# Practica.net
KiCad netlist of a schematic drawn in Altium Designer
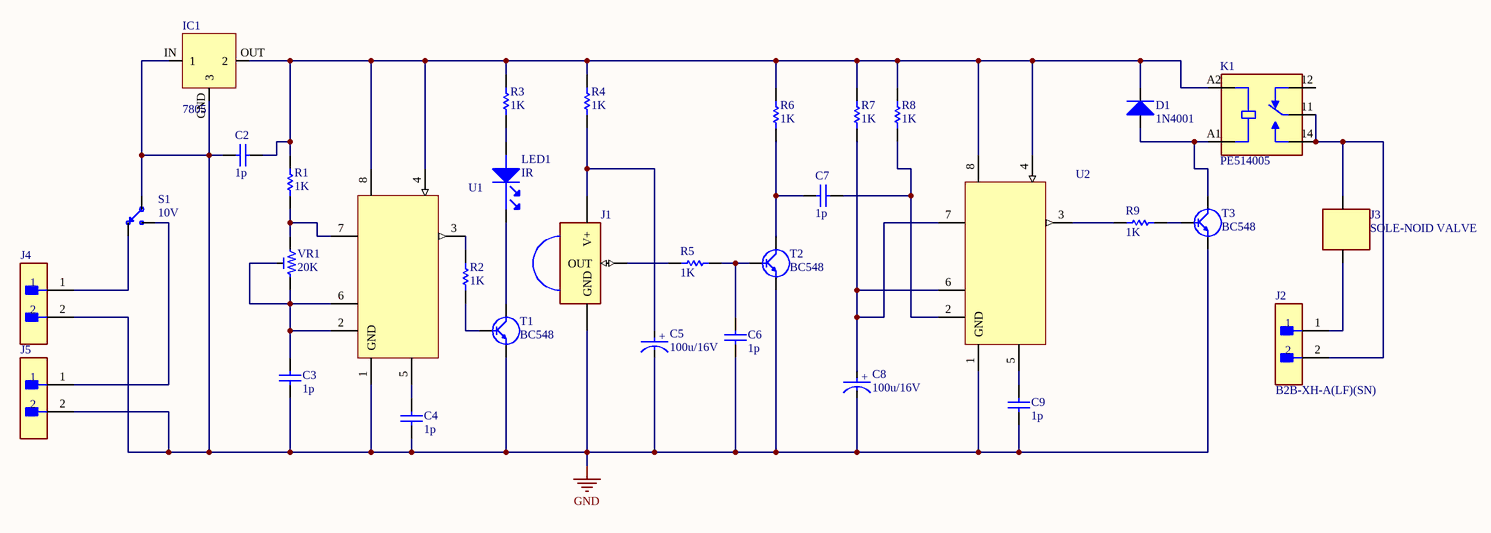
[diagram p0: Practica.SchDoc]

(export (version "E")
  (design (tool "Eeschema 10.0.6"))
  (components
    (comp (ref "C2")
      (value "1p")
      (footprint "CAPC1005X55N")
      (description "Capacitor")
      (libsource (lib "Practica_Schlib1") (part "Capacitor"))
    )
    (comp (ref "C3")
      (value "1p")
      (footprint "CAPC1005X55N")
      (description "Capacitor")
      (libsource (lib "Practica_Schlib1") (part "Capacitor"))
    )
    (comp (ref "C4")
      (value "1p")
      (footprint "CAPC1005X55N")
      (description "Capacitor")
      (libsource (lib "Practica_Schlib1") (part "Capacitor"))
    )
    (comp (ref "C5")
      (value "100u/16V")
      (footprint "WCAP-ASLI_D4H5.5")
      (description "15uF 6.3V  ±20% 3.5Ω 1206  SMD Tantalum Capacitor")
      (fields (field (name "TOLERANCE") "20%") (field (name "MANUFACTURER") "Wurth Electronics"))
      (libsource (lib "Practica_Schlib1") (part "a00bbbee19879c290e62620ae7e47b1"))
    )
    (comp (ref "C6")
      (value "1p")
      (footprint "CAPC1005X55N")
      (description "Capacitor")
      (libsource (lib "Practica_Schlib1") (part "Capacitor"))
    )
    (comp (ref "C7")
      (value "1p")
      (footprint "CAPC1005X55N")
      (description "Capacitor")
      (libsource (lib "Practica_Schlib1") (part "Capacitor"))
    )
    (comp (ref "C8")
      (value "100u/16V")
      (footprint "WCAP-ASLI_D4H5.5")
      (description "15uF 6.3V  ±20% 3.5Ω 1206  SMD Tantalum Capacitor")
      (fields (field (name "TOLERANCE") "20%") (field (name "MANUFACTURER") "Wurth Electronics"))
      (libsource (lib "Practica_Schlib1") (part "a00bbbee19879c290e62620ae7e47b1"))
    )
    (comp (ref "C9")
      (value "1p")
      (footprint "CAPC1005X55N")
      (description "Capacitor")
      (libsource (lib "Practica_Schlib1") (part "Capacitor"))
    )
    (comp (ref "D1")
      (value "1N4001")
      (footprint "DIOAD1036W78L470D235")
      (fields (field (name "MANUFACTURER") "Good-Ark"))
      (libsource (lib "Practica_Schlib1") (part "1N4001"))
    )
    (comp (ref "IC1")
      (value "7805")
      (footprint "78XXS")
      (description "Fixed Positive Standard Regulator, 5VBIPolar, PSSO2")
      (fields (field (name "MANUFACTURER") "onsemi") (field (name "MANUFACTURER PART NUMBER") "MC7805BDTG"))
      (libsource (lib "Practica_Schlib1") (part "IC1"))
    )
    (comp (ref "J1")
      (value "TSOP1738")
      (footprint "TSOP17XX")
      (description "IR Remote Receiver 38KHz 35m 3-Pin")
      (fields (field (name "MP") "TSOP1738.") (field (name "MF") "Vishay"))
      (libsource (lib "Practica_Schlib1") (part "TSOP1738"))
    )
    (comp (ref "J2")
      (value "B2B-XH-A(LF)(SN)")
      (footprint "FP-B2B-XH-A_LF_SN-MFG")
      (description "CONN HEADER VERT 2POS 2.5MM")
      (libsource (lib "Practica_Schlib1") (part "CON2"))
    )
    (comp (ref "J3")
      (value "SOLE-NOID VALVE")
      (footprint "PHOENIX_1904147")
      (fields (field (name "MF") "Phoenix Contact") (field (name "MP") "1904147"))
      (libsource (lib "Practica_Schlib1") (part "SOLE-NOID VALVE"))
    )
    (comp (ref "J4")
      (value "B2B-XH-A(LF)(SN)")
      (footprint "FP-B2B-XH-A_LF_SN-MFG")
      (description "CONN HEADER VERT 2POS 2.5MM")
      (libsource (lib "Practica_Schlib1") (part "CON2"))
    )
    (comp (ref "J5")
      (value "B2B-XH-A(LF)(SN)")
      (footprint "FP-B2B-XH-A_LF_SN-MFG")
      (description "CONN HEADER VERT 2POS 2.5MM")
      (libsource (lib "Practica_Schlib1") (part "CON2"))
    )
    (comp (ref "K1")
      (value "PE514005")
      (footprint "RELAY_PE514005")
      (description "Shrack, Relay,miniature,PCB,SPDT,5A,5Vdc coil, 1-1393219-7 ¦ TE Connectivity PE514005")
      (fields (field (name "MF") "TE Connectivity"))
      (libsource (lib "Practica_Schlib1") (part "PE514005"))
    )
    (comp (ref "LED1")
      (value "IR")
      (footprint "LED3MM")
      (description "LED SM 0603 3V -/1000/-MCD GREEN")
      (fields
        (field (name "MANUFACTURER") "Visual Communications")
        (field (name "MANUFACTURER PART NUMBER") "LSM0603453V")
      )
      (libsource (lib "Practica_Schlib1") (part "LED"))
    )
    (comp (ref "R1")
      (value "1K")
      (footprint "RESC1005X40N")
      (description "Resistor")
      (libsource (lib "Practica_Schlib1") (part "Resistor"))
    )
    (comp (ref "R2")
      (value "1K")
      (footprint "RESC1005X40N")
      (description "Resistor")
      (libsource (lib "Practica_Schlib1") (part "Resistor"))
    )
    (comp (ref "R3")
      (value "1K")
      (footprint "RESC1005X40N")
      (description "Resistor")
      (libsource (lib "Practica_Schlib1") (part "Resistor"))
    )
    (comp (ref "R4")
      (value "1K")
      (footprint "RESC1005X40N")
      (description "Resistor")
      (libsource (lib "Practica_Schlib1") (part "Resistor"))
    )
    (comp (ref "R5")
      (value "1K")
      (footprint "RESC1005X40N")
      (description "Resistor")
      (libsource (lib "Practica_Schlib1") (part "Resistor"))
    )
    (comp (ref "R6")
      (value "1K")
      (footprint "RESC1005X40N")
      (description "Resistor")
      (libsource (lib "Practica_Schlib1") (part "Resistor"))
    )
    (comp (ref "R7")
      (value "1K")
      (footprint "RESC1005X40N")
      (description "Resistor")
      (libsource (lib "Practica_Schlib1") (part "Resistor"))
    )
    (comp (ref "R8")
      (value "1K")
      (footprint "RESC1005X40N")
      (description "Resistor")
      (libsource (lib "Practica_Schlib1") (part "Resistor"))
    )
    (comp (ref "R9")
      (value "1K")
      (footprint "RESC1005X40N")
      (description "Resistor")
      (libsource (lib "Practica_Schlib1") (part "Resistor"))
    )
    (comp (ref "S1")
      (value "10V")
      (footprint "SW_A101SYZQ04")
      (description "Toggle Switch")
      (fields
        (field (name "MANUFACTURER") "E-Switch")
        (field (name "MANUFACTURER PART NUMBER") "100SP2T1B1M1QEH")
      )
      (libsource (lib "Practica_Schlib1") (part "switch"))
    )
    (comp (ref "T1")
      (value "BC548")
      (footprint "TO92250P510H770-3")
      (description "Bipolar (BJT) Transistor NPN 30 V 100 mA 300MHz 500 mW Through Hole TO-92-3")
      (fields (field (name "MANUFACTURER") "onsemi"))
      (libsource (lib "Practica_Schlib1") (part "BC548"))
    )
    (comp (ref "T2")
      (value "BC548")
      (footprint "TO92250P510H770-3")
      (description "Bipolar (BJT) Transistor NPN 30 V 100 mA 300MHz 500 mW Through Hole TO-92-3")
      (fields (field (name "MANUFACTURER") "onsemi"))
      (libsource (lib "Practica_Schlib1") (part "BC548"))
    )
    (comp (ref "T3")
      (value "BC548")
      (footprint "TO92250P510H770-3")
      (description "Bipolar (BJT) Transistor NPN 30 V 100 mA 300MHz 500 mW Through Hole TO-92-3")
      (fields (field (name "MANUFACTURER") "onsemi"))
      (libsource (lib "Practica_Schlib1") (part "BC548"))
    )
    (comp (ref "U1")
      (value "LMC555CMM/NOPB")
      (footprint "DGK0008A_L")
      (description "CMOS Timer, 8-pin Mini SOIC, Pb-Free")
      (fields (field (name "MANUFACTURER") "Texas Instruments"))
      (libsource (lib "Practica_Schlib1") (part "LM555"))
    )
    (comp (ref "U2")
      (value "LMC555CMM/NOPB")
      (footprint "DGK0008A_L")
      (description "CMOS Timer, 8-pin Mini SOIC, Pb-Free")
      (fields (field (name "MANUFACTURER") "Texas Instruments"))
      (libsource (lib "Practica_Schlib1") (part "LM555"))
    )
    (comp (ref "VR1")
      (value "20K")
      (footprint "TRIM_PV36W203C01B00")
      (description "20 kOhms 0.5W, 1/2W PC Pins Through Hole Trimmer Potentiometer Cermet 25.0 Turn Top Adjustment")
      (fields
        (field (name "MANUFACTURER") "Bourns")
        (field (name "MANUFACTURER PART NUMBER") "PV36W203C01B00")
      )
      (libsource (lib "Practica_Schlib1") (part "VR"))
    )
  )
  (nets
    (net (code "1") (name "GND") (class "Default")
      (node (ref "C2") (pin "1") (pinfunction "1_1") (pintype "passive"))
      (node (ref "C3") (pin "1") (pinfunction "1_1") (pintype "passive"))
      (node (ref "C4") (pin "1") (pinfunction "1_1") (pintype "passive"))
      (node (ref "C5") (pin "1") (pinfunction "C_1") (pintype "passive"))
      (node (ref "C6") (pin "1") (pinfunction "1_1") (pintype "passive"))
      (node (ref "C8") (pin "1") (pinfunction "C_1") (pintype "passive"))
      (node (ref "C9") (pin "1") (pinfunction "1_1") (pintype "passive"))
      (node (ref "IC1") (pin "GND") (pinfunction "3_GND") (pintype "passive"))
      (node (ref "IC1") (pin "IN") (pinfunction "1_IN") (pintype "passive"))
      (node (ref "J1") (pin "GND") (pinfunction "GND_GND") (pintype "power_in"))
      (node (ref "J4") (pin "2") (pinfunction "2_2") (pintype "passive"))
      (node (ref "J5") (pin "2") (pinfunction "2_2") (pintype "passive"))
      (node (ref "S1") (pin "3") (pinfunction "3_3") (pintype "passive"))
      (node (ref "T1") (pin "3") (pinfunction "3_3") (pintype "passive"))
      (node (ref "T2") (pin "3") (pinfunction "3_3") (pintype "passive"))
      (node (ref "T3") (pin "3") (pinfunction "3_3") (pintype "passive"))
      (node (ref "U1") (pin "1") (pinfunction "GND_1") (pintype "power_in"))
      (node (ref "U2") (pin "1") (pinfunction "GND_1") (pintype "power_in"))
    )
    (net (code "2") (name "Net-(C5-A)") (class "Default")
      (node (ref "C5") (pin "2") (pinfunction "A_2") (pintype "passive"))
      (node (ref "J1") (pin "V+") (pinfunction "V+_V+") (pintype "power_in"))
      (node (ref "R4") (pin "1") (pinfunction "1_1") (pintype "passive"))
    )
    (net (code "3") (name "Net-(C6-Pad2)") (class "Default")
      (node (ref "C6") (pin "2") (pinfunction "2_2") (pintype "passive"))
      (node (ref "R5") (pin "1") (pinfunction "1_1") (pintype "passive"))
      (node (ref "T2") (pin "1") (pinfunction "1_1") (pintype "passive"))
    )
    (net (code "4") (name "Net-(C7-Pad1)") (class "Default")
      (node (ref "C7") (pin "1") (pinfunction "1_1") (pintype "passive"))
      (node (ref "R6") (pin "1") (pinfunction "1_1") (pintype "passive"))
      (node (ref "T2") (pin "2") (pinfunction "2_2") (pintype "passive"))
    )
    (net (code "5") (name "Net-(C8-A)") (class "Default")
      (node (ref "C8") (pin "2") (pinfunction "A_2") (pintype "passive"))
      (node (ref "R7") (pin "1") (pinfunction "1_1") (pintype "passive"))
      (node (ref "U2") (pin "6") (pinfunction "THR_6") (pintype "passive"))
      (node (ref "U2") (pin "7") (pinfunction "DIS_7") (pintype "open_collector"))
    )
    (net (code "6") (name "Net-(D1-1)") (class "Default")
      (node (ref "D1") (pin "A") (pinfunction "1_A") (pintype "passive"))
      (node (ref "K1") (pin "A1") (pinfunction "COIL2_A1") (pintype "passive"))
      (node (ref "T3") (pin "2") (pinfunction "2_2") (pintype "passive"))
    )
    (net (code "7") (name "Net-(D1-2)") (class "Default")
      (node (ref "C2") (pin "2") (pinfunction "2_2") (pintype "passive"))
      (node (ref "D1") (pin "C") (pinfunction "2_C") (pintype "passive"))
      (node (ref "IC1") (pin "OUT") (pinfunction "2_OUT") (pintype "power_in"))
      (node (ref "K1") (pin "A2") (pinfunction "COIL1_A2") (pintype "passive"))
      (node (ref "R1") (pin "2") (pinfunction "2_2") (pintype "passive"))
      (node (ref "R3") (pin "2") (pinfunction "2_2") (pintype "passive"))
      (node (ref "R4") (pin "2") (pinfunction "2_2") (pintype "passive"))
      (node (ref "R6") (pin "2") (pinfunction "2_2") (pintype "passive"))
      (node (ref "R7") (pin "2") (pinfunction "2_2") (pintype "passive"))
      (node (ref "R8") (pin "2") (pinfunction "2_2") (pintype "passive"))
      (node (ref "U1") (pin "4") (pinfunction "~{RST}_4") (pintype "input"))
      (node (ref "U1") (pin "8") (pinfunction "V+_8") (pintype "passive"))
      (node (ref "U2") (pin "4") (pinfunction "~{RST}_4") (pintype "input"))
      (node (ref "U2") (pin "8") (pinfunction "V+_8") (pintype "passive"))
    )
    (net (code "8") (name "Net-(J1-PadOUT)") (class "Default")
      (node (ref "J1") (pin "OUT") (pinfunction "OUT_OUT") (pintype "bidirectional"))
      (node (ref "R5") (pin "2") (pinfunction "2_2") (pintype "passive"))
    )
    (net (code "9") (name "Net-(J2-Pad1)") (class "Default")
      (node (ref "J2") (pin "1") (pinfunction "1_1") (pintype "passive"))
      (node (ref "J3") (pin "2") (pinfunction "2_2") (pintype "passive"))
    )
    (net (code "10") (name "Net-(J4-Pad1)") (class "Default")
      (node (ref "J4") (pin "1") (pinfunction "1_1") (pintype "passive"))
      (node (ref "S1") (pin "2") (pinfunction "2_2") (pintype "passive"))
    )
    (net (code "11") (name "Net-(J5-Pad1)") (class "Default")
      (node (ref "J5") (pin "1") (pinfunction "1_1") (pintype "passive"))
      (node (ref "S1") (pin "1") (pinfunction "1_1") (pintype "passive"))
    )
    (net (code "12") (name "Net-(K1-COM)") (class "Default")
      (node (ref "J2") (pin "2") (pinfunction "2_2") (pintype "passive"))
      (node (ref "J3") (pin "1") (pinfunction "1_1") (pintype "passive"))
      (node (ref "K1") (pin "11") (pinfunction "COM_11") (pintype "passive"))
      (node (ref "K1") (pin "14") (pinfunction "NO_14") (pintype "passive"))
    )
    (net (code "13") (name "Net-(LED1-1)") (class "Default")
      (node (ref "LED1") (pin "K") (pinfunction "1_K") (pintype "passive"))
      (node (ref "T1") (pin "2") (pinfunction "2_2") (pintype "passive"))
    )
    (net (code "14") (name "Net-(LED1-2)") (class "Default")
      (node (ref "LED1") (pin "A") (pinfunction "2_A") (pintype "passive"))
      (node (ref "R3") (pin "1") (pinfunction "1_1") (pintype "passive"))
    )
    (net (code "15") (name "Net-(R2-Pad1)") (class "Default")
      (node (ref "R2") (pin "1") (pinfunction "1_1") (pintype "passive"))
      (node (ref "T1") (pin "1") (pinfunction "1_1") (pintype "passive"))
    )
    (net (code "16") (name "Net-(R9-Pad2)") (class "Default")
      (node (ref "R9") (pin "2") (pinfunction "2_2") (pintype "passive"))
      (node (ref "T3") (pin "1") (pinfunction "1_1") (pintype "passive"))
    )
    (net (code "17") (name "Net-(U1-CVOLT)") (class "Default")
      (node (ref "C4") (pin "2") (pinfunction "2_2") (pintype "passive"))
      (node (ref "U1") (pin "5") (pinfunction "CVOLT_5") (pintype "passive"))
    )
    (net (code "18") (name "Net-(U1-DIS)") (class "Default")
      (node (ref "R1") (pin "1") (pinfunction "1_1") (pintype "passive"))
      (node (ref "U1") (pin "7") (pinfunction "DIS_7") (pintype "open_collector"))
      (node (ref "VR1") (pin "1") (pinfunction "1_1") (pintype "passive"))
    )
    (net (code "19") (name "Net-(U1-OUT)") (class "Default")
      (node (ref "R2") (pin "2") (pinfunction "2_2") (pintype "passive"))
      (node (ref "U1") (pin "3") (pinfunction "OUT_3") (pintype "output"))
    )
    (net (code "20") (name "Net-(U1-THR)") (class "Default")
      (node (ref "C3") (pin "2") (pinfunction "2_2") (pintype "passive"))
      (node (ref "U1") (pin "2") (pinfunction "~{TRIG}_2") (pintype "passive"))
      (node (ref "U1") (pin "6") (pinfunction "THR_6") (pintype "passive"))
      (node (ref "VR1") (pin "2") (pinfunction "2_2") (pintype "passive"))
      (node (ref "VR1") (pin "3") (pinfunction "3_3") (pintype "passive"))
    )
    (net (code "21") (name "Net-(U2-CVOLT)") (class "Default")
      (node (ref "C9") (pin "2") (pinfunction "2_2") (pintype "passive"))
      (node (ref "U2") (pin "5") (pinfunction "CVOLT_5") (pintype "passive"))
    )
    (net (code "22") (name "Net-(U2-OUT)") (class "Default")
      (node (ref "R9") (pin "1") (pinfunction "1_1") (pintype "passive"))
      (node (ref "U2") (pin "3") (pinfunction "OUT_3") (pintype "output"))
    )
    (net (code "23") (name "Net-(U2-~{TRIG})") (class "Default")
      (node (ref "C7") (pin "2") (pinfunction "2_2") (pintype "passive"))
      (node (ref "R8") (pin "1") (pinfunction "1_1") (pintype "passive"))
      (node (ref "U2") (pin "2") (pinfunction "~{TRIG}_2") (pintype "passive"))
    )
    (net (code "24") (name "unconnected-(K1-NC-Pad12)") (class "Default")
      (node (ref "K1") (pin "12") (pinfunction "NC_12") (pintype "passive"))
    )
  )
)
